# ASTABLE_555_timer.net
KiCad netlist of a schematic drawn in EAGLE
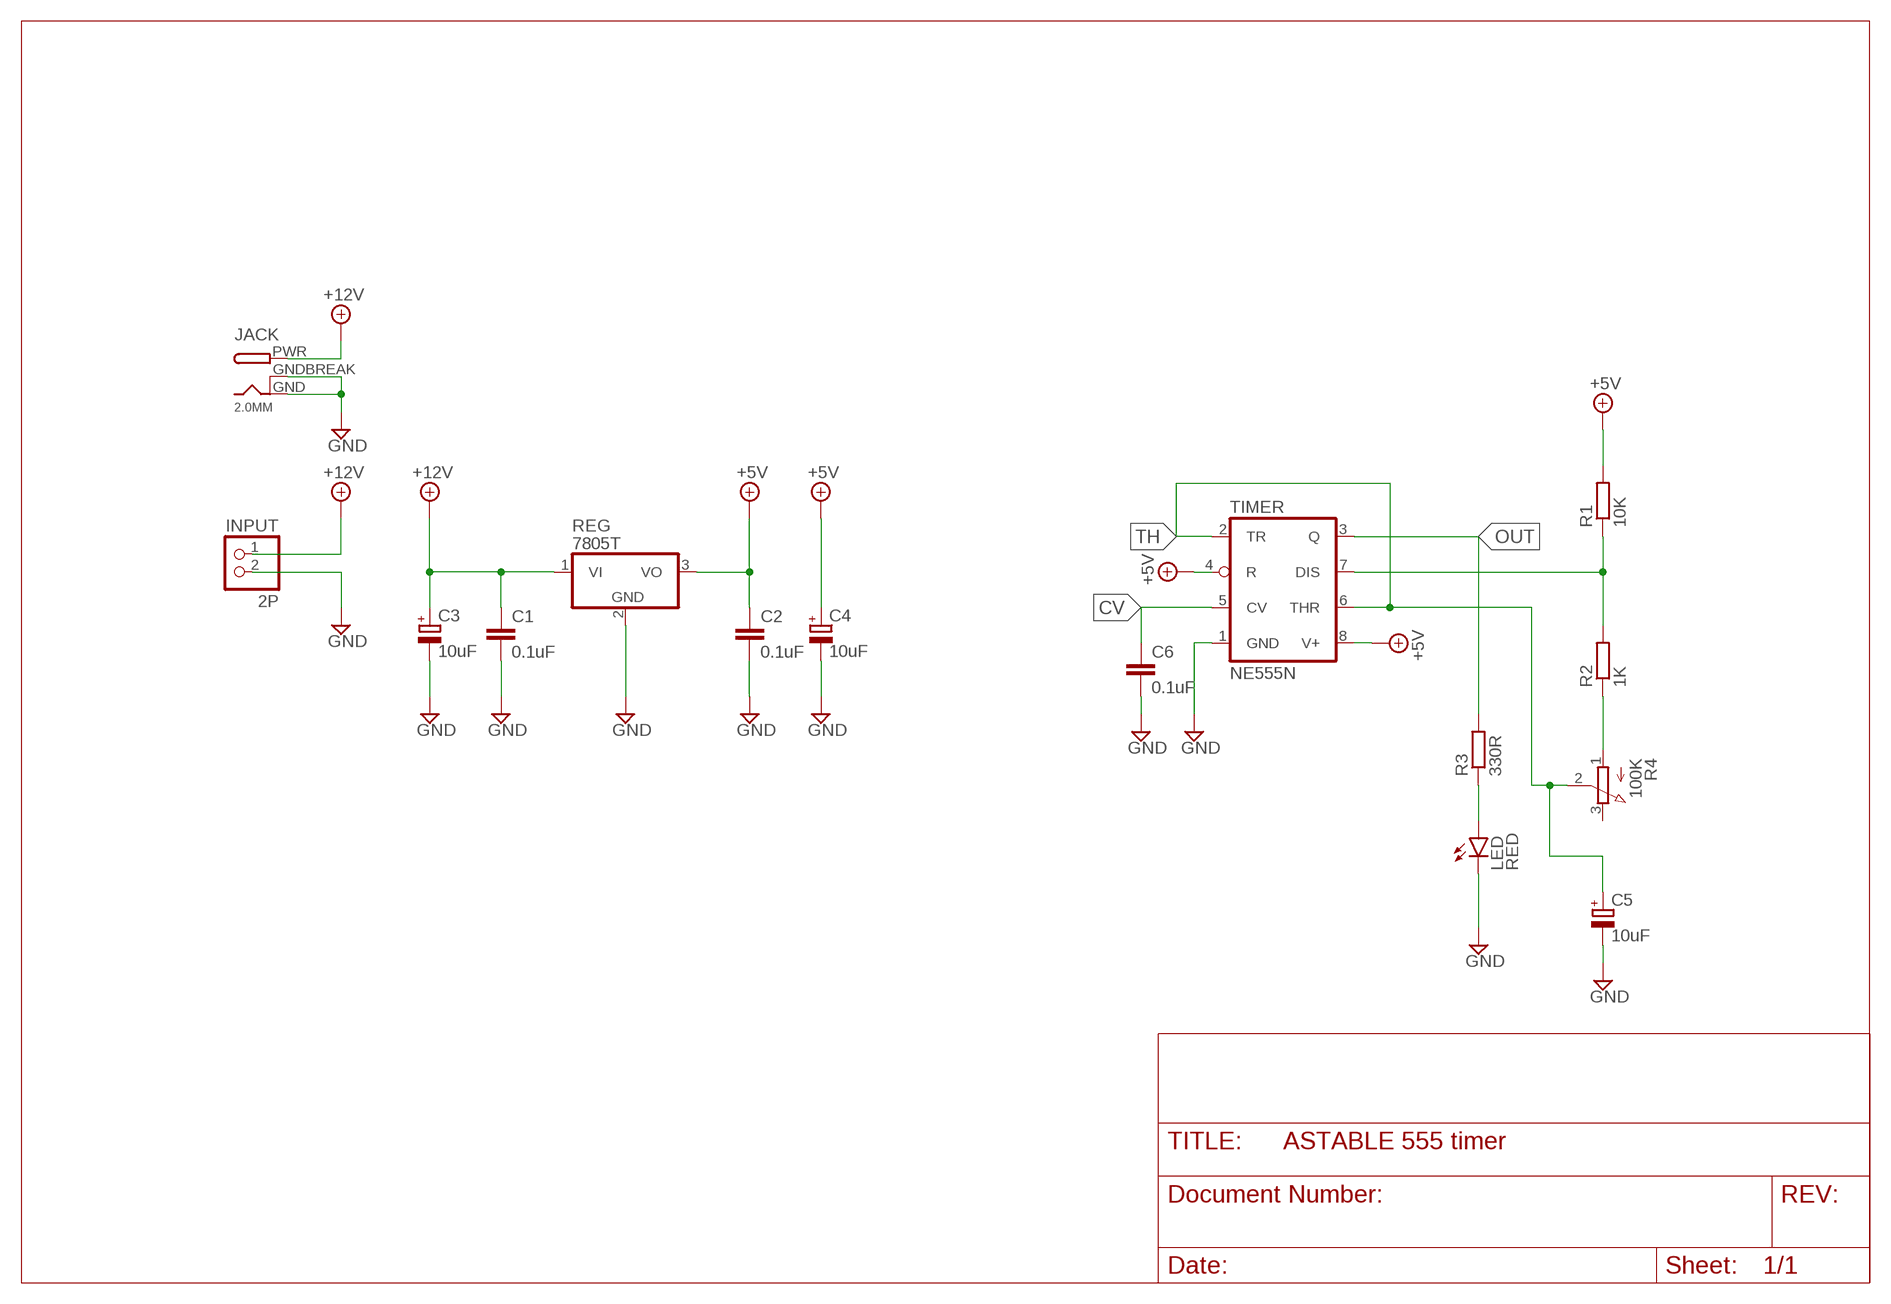
[diagram p0: schematic, sheet 1]

(export (version "E")
  (design (tool "Eeschema 10.0.6"))
  (components
    (comp (ref "C1")
      (value "0.1uF")
      (footprint "eagle-import:C050-030X075")
      (libsource (lib "eagle-import") (part "C-EU050-030X075"))
    )
    (comp (ref "C2")
      (value "0.1uF")
      (footprint "eagle-import:C050-030X075")
      (libsource (lib "eagle-import") (part "C-EU050-030X075"))
    )
    (comp (ref "C3")
      (value "10uF")
      (footprint "eagle-import:E3,5-8")
      (libsource (lib "eagle-import") (part "CPOL-EUE3.5-8"))
    )
    (comp (ref "C4")
      (value "10uF")
      (footprint "eagle-import:E3,5-8")
      (libsource (lib "eagle-import") (part "CPOL-EUE3.5-8"))
    )
    (comp (ref "C5")
      (value "10uF")
      (footprint "eagle-import:E3,5-8")
      (libsource (lib "eagle-import") (part "CPOL-EUE3.5-8"))
    )
    (comp (ref "C6")
      (value "0.1uF")
      (footprint "eagle-import:C050-030X075")
      (libsource (lib "eagle-import") (part "C-EU050-030X075"))
    )
    (comp (ref "INPUT")
      (value "2P")
      (footprint "eagle-import:1X02")
      (libsource (lib "eagle-import") (part "PINHD-1X2"))
    )
    (comp (ref "JACK")
      (value "2.0MM")
      (footprint "eagle-import:DCJACK_2MM_PTH")
      (libsource (lib "eagle-import") (part "DCBARRELPTH"))
    )
    (comp (ref "LED")
      (value "RED")
      (footprint "eagle-import:LED5MM")
      (libsource (lib "eagle-import") (part "LED5MM"))
    )
    (comp (ref "R1")
      (value "10K")
      (footprint "eagle-import:0207_10")
      (libsource (lib "eagle-import") (part "R-EU_0207/10"))
    )
    (comp (ref "R2")
      (value "1K")
      (footprint "eagle-import:0207_10")
      (libsource (lib "eagle-import") (part "R-EU_0207/10"))
    )
    (comp (ref "R3")
      (value "330R")
      (footprint "eagle-import:0207_10")
      (libsource (lib "eagle-import") (part "R-EU_0207/10"))
    )
    (comp (ref "R4")
      (value "100K")
      (footprint "eagle-import:3RP_1610N")
      (libsource (lib "eagle-import") (part "3RP/1610N"))
    )
    (comp (ref "REG")
      (value "7805T")
      (footprint "eagle-import:TO220H")
      (libsource (lib "eagle-import") (part "78T05"))
    )
    (comp (ref "TIMER")
      (value "NE555N")
      (footprint "eagle-import:DIL08")
      (libsource (lib "eagle-import") (part "555NNE"))
    )
  )
  (nets
    (net (code "1") (name "+5V") (class "Default")
      (node (ref "C2") (pin "1") (pinfunction "1_1") (pintype "passive"))
      (node (ref "C4") (pin "+") (pinfunction "+_+") (pintype "passive"))
      (node (ref "R1") (pin "2") (pinfunction "2_2") (pintype "passive"))
      (node (ref "REG") (pin "3") (pinfunction "VO_3") (pintype "passive"))
      (node (ref "TIMER") (pin "4") (pinfunction "R_4") (pintype "input"))
      (node (ref "TIMER") (pin "8") (pinfunction "V+_8") (pintype "power_in"))
    )
    (net (code "2") (name "+12V") (class "Default")
      (node (ref "C1") (pin "1") (pinfunction "1_1") (pintype "passive"))
      (node (ref "C3") (pin "+") (pinfunction "+_+") (pintype "passive"))
      (node (ref "INPUT") (pin "1") (pinfunction "1_1") (pintype "passive"))
      (node (ref "JACK") (pin "PWR") (pinfunction "PWR_PWR") (pintype "power_in"))
      (node (ref "REG") (pin "1") (pinfunction "VI_1") (pintype "input"))
    )
    (net (code "3") (name "CV") (class "Default")
      (node (ref "C6") (pin "1") (pinfunction "1_1") (pintype "passive"))
      (node (ref "TIMER") (pin "5") (pinfunction "CV_5") (pintype "input"))
    )
    (net (code "4") (name "GND") (class "Default")
      (node (ref "C1") (pin "2") (pinfunction "2_2") (pintype "passive"))
      (node (ref "C2") (pin "2") (pinfunction "2_2") (pintype "passive"))
      (node (ref "C3") (pin "-") (pinfunction "-_-") (pintype "passive"))
      (node (ref "C4") (pin "-") (pinfunction "-_-") (pintype "passive"))
      (node (ref "C5") (pin "-") (pinfunction "-_-") (pintype "passive"))
      (node (ref "C6") (pin "2") (pinfunction "2_2") (pintype "passive"))
      (node (ref "INPUT") (pin "2") (pinfunction "2_2") (pintype "passive"))
      (node (ref "JACK") (pin "GND") (pinfunction "GND_GND") (pintype "power_in"))
      (node (ref "JACK") (pin "GNDBREAK") (pinfunction "GNDBREAK_GNDBREAK") (pintype "power_in"))
      (node (ref "LED") (pin "K") (pinfunction "C_K") (pintype "passive"))
      (node (ref "REG") (pin "2") (pinfunction "GND_2") (pintype "passive"))
      (node (ref "TIMER") (pin "1") (pinfunction "GND_1") (pintype "power_in"))
    )
    (net (code "5") (name "Net-(LED-PadA)") (class "Default")
      (node (ref "LED") (pin "A") (pinfunction "A_A") (pintype "passive"))
      (node (ref "R3") (pin "1") (pinfunction "1_1") (pintype "passive"))
    )
    (net (code "6") (name "Net-(R4-A)") (class "Default")
      (node (ref "R2") (pin "1") (pinfunction "1_1") (pintype "passive"))
      (node (ref "R4") (pin "1") (pinfunction "A_1") (pintype "passive"))
    )
    (net (code "7") (name "Net-(TIMER-DIS)") (class "Default")
      (node (ref "R1") (pin "1") (pinfunction "1_1") (pintype "passive"))
      (node (ref "R2") (pin "2") (pinfunction "2_2") (pintype "passive"))
      (node (ref "TIMER") (pin "7") (pinfunction "DIS_7") (pintype "input"))
    )
    (net (code "8") (name "OUT") (class "Default")
      (node (ref "R3") (pin "2") (pinfunction "2_2") (pintype "passive"))
      (node (ref "TIMER") (pin "3") (pinfunction "Q_3") (pintype "output"))
    )
    (net (code "9") (name "TH") (class "Default")
      (node (ref "C5") (pin "+") (pinfunction "+_+") (pintype "passive"))
      (node (ref "R4") (pin "2") (pinfunction "S_2") (pintype "passive"))
      (node (ref "TIMER") (pin "2") (pinfunction "TR_2") (pintype "input"))
      (node (ref "TIMER") (pin "6") (pinfunction "THR_6") (pintype "input"))
    )
    (net (code "10") (name "unconnected-(R4-E-Pad3)") (class "Default")
      (node (ref "R4") (pin "3") (pinfunction "E_3") (pintype "passive"))
    )
  )
)
